# SAMV71_Xplained_Ultra_Ethernet.net
KiCad netlist of a schematic drawn in Altium Designer
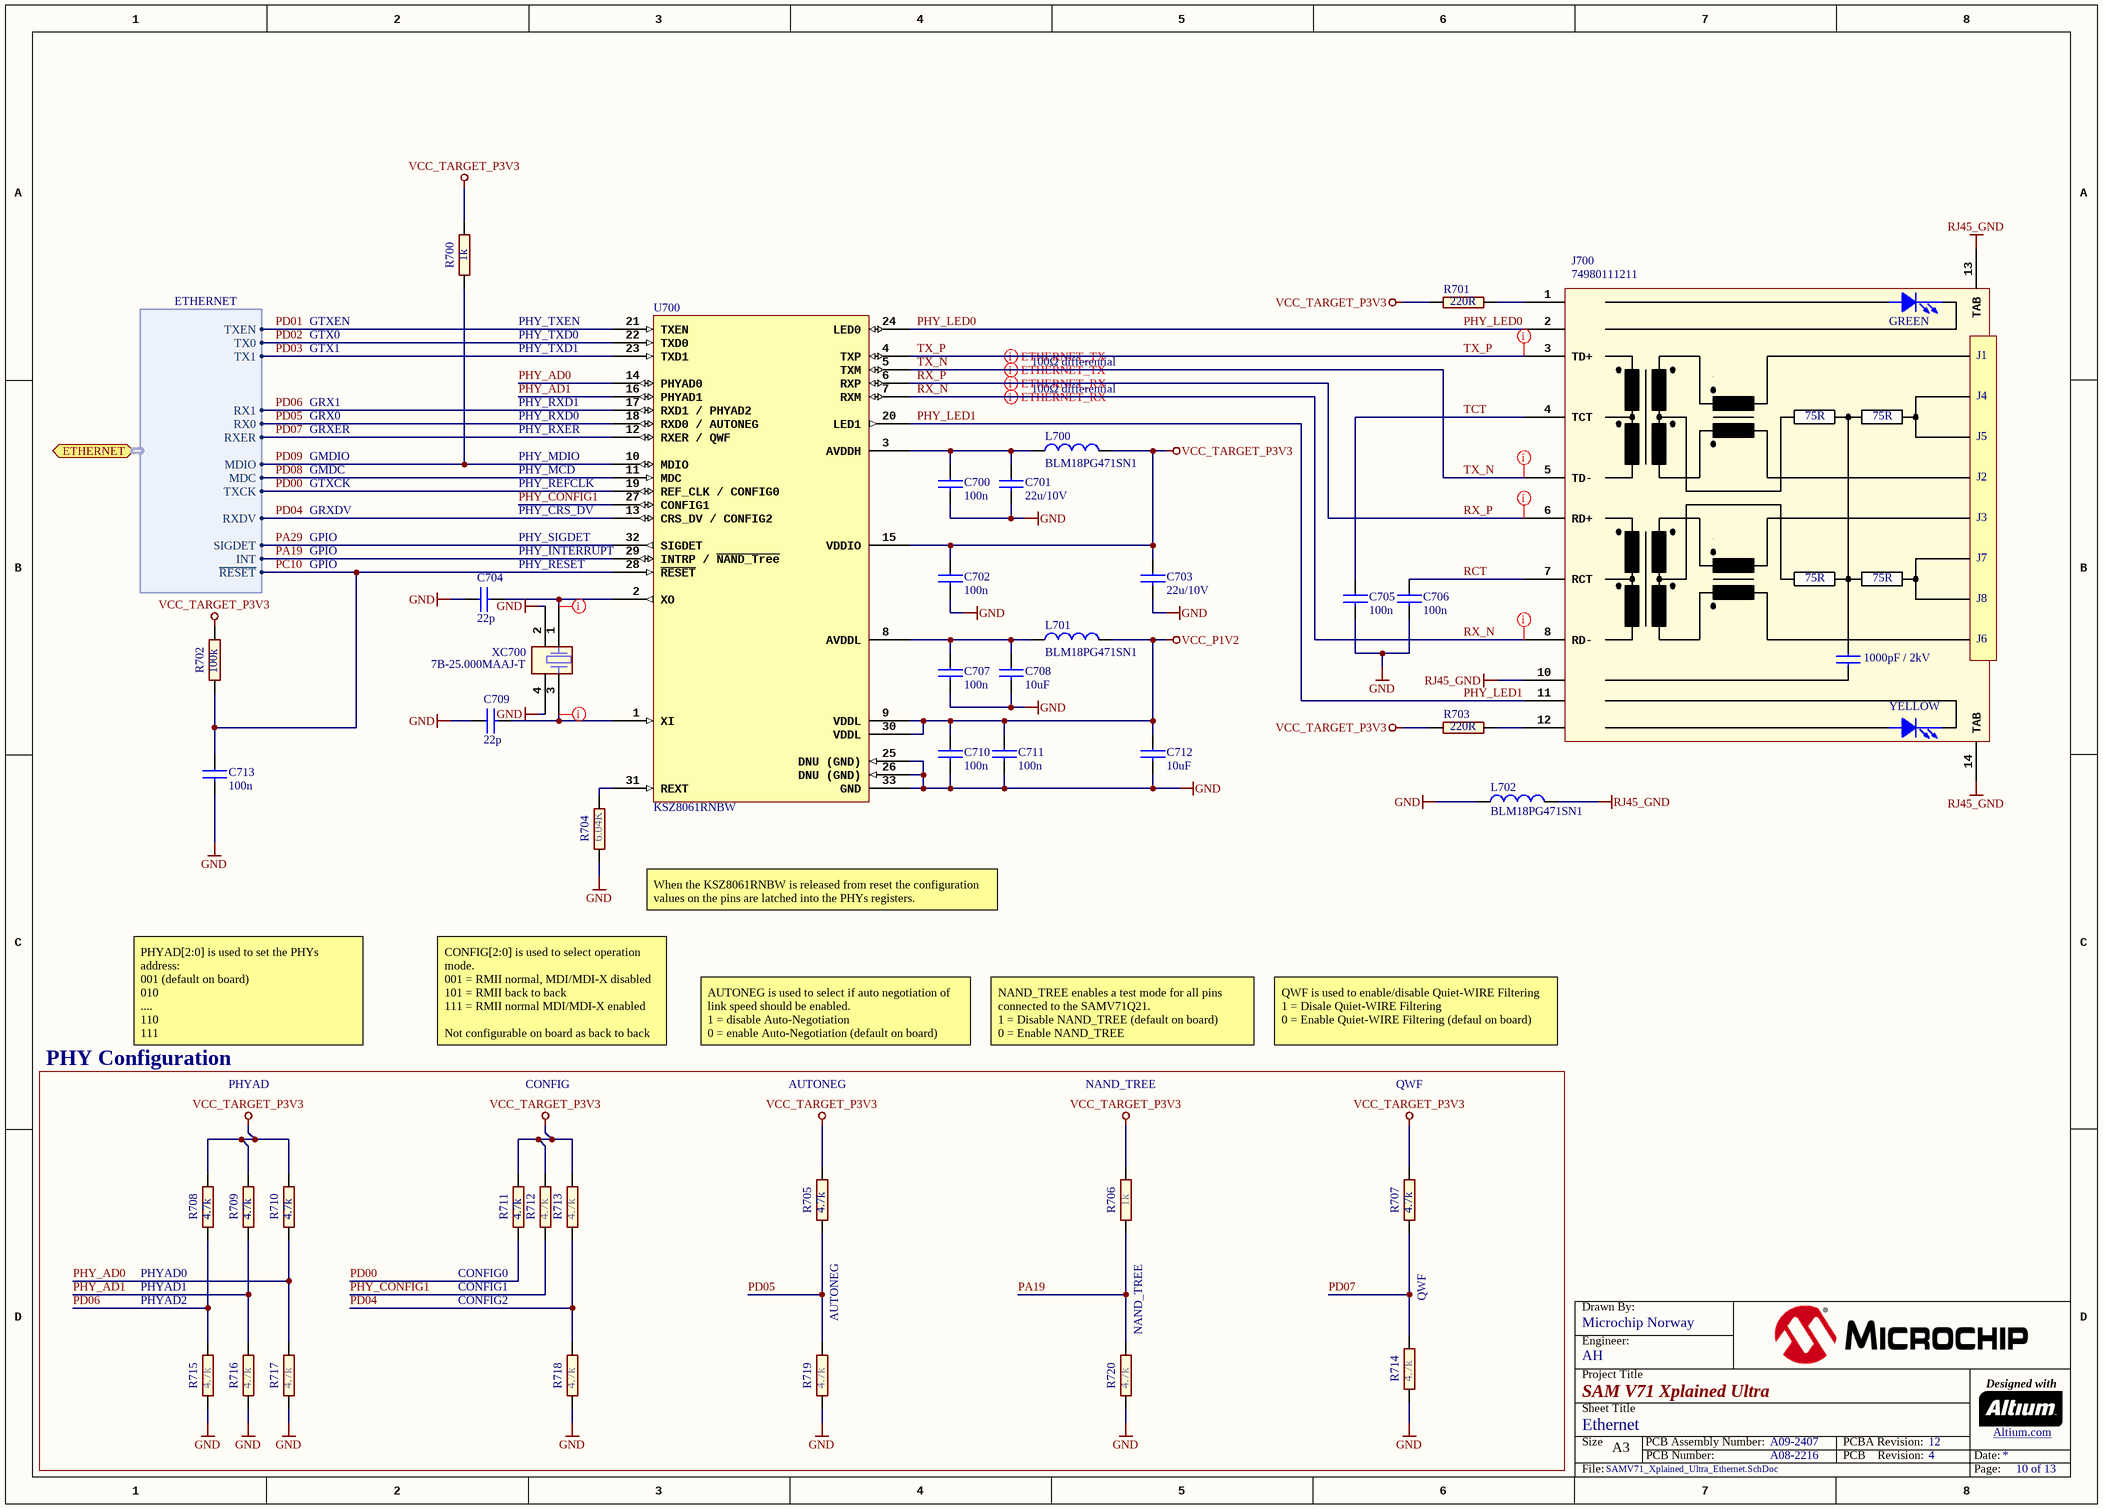
[diagram p0: SAMV71_Xplained_Ultra_Ethernet.SchDoc]

(export (version "E")
  (design (tool "Eeschema 10.0.6"))
  (components
    (comp (ref "C700")
      (value "100n")
      (footprint "AP1-00001")
      (description "Ceramic capacitor, SMD 0402, X7R, 16V, +/-10%")
      (fields (field (name "TOLERANCE") "16V, +/-10%") (field (name "MANUFACTURER") "Kemet"))
      (libsource (lib "AltiumDbLib") (part "CAP-NONPOL"))
    )
    (comp (ref "C701")
      (value "22u/10V")
      (footprint "AP1-00003")
      (description "Ceramic capacitor, SMD 0805, X5R, 10V, ±20%")
      (fields (field (name "MANUFACTURER") "tdk") (field (name "MPN") "C2012X5R1A226M/0.85"))
      (libsource (lib "AltiumDbLib") (part "CAP-NONPOL"))
    )
    (comp (ref "C702")
      (value "100n")
      (footprint "AP1-00001")
      (description "Ceramic capacitor, SMD 0402, X7R, 16V, +/-10%")
      (fields (field (name "TOLERANCE") "16V, +/-10%") (field (name "MANUFACTURER") "Kemet"))
      (libsource (lib "AltiumDbLib") (part "CAP-NONPOL"))
    )
    (comp (ref "C703")
      (value "22u/10V")
      (footprint "AP1-00003")
      (description "Ceramic capacitor, SMD 0805, X5R, 10V, ±20%")
      (fields (field (name "MANUFACTURER") "tdk") (field (name "MPN") "C2012X5R1A226M/0.85"))
      (libsource (lib "AltiumDbLib") (part "CAP-NONPOL"))
    )
    (comp (ref "C704")
      (value "22p")
      (footprint "AP1-00001")
      (description "Ceramic capacitor, SMD 0402, NP0, 50V, +/-5%")
      (fields (field (name "TOLERANCE") "50V, +/-5%") (field (name "MANUFACTURER") "YAGEO CORP"))
      (libsource (lib "AltiumDbLib") (part "CAP-NONPOL"))
    )
    (comp (ref "C705")
      (value "100n")
      (footprint "AP1-00001")
      (description "Ceramic capacitor, SMD 0402, X7R, 16V, +/-10%")
      (fields (field (name "TOLERANCE") "16V, +/-10%") (field (name "MANUFACTURER") "Kemet"))
      (libsource (lib "AltiumDbLib") (part "CAP-NONPOL"))
    )
    (comp (ref "C706")
      (value "100n")
      (footprint "AP1-00001")
      (description "Ceramic capacitor, SMD 0402, X7R, 16V, +/-10%")
      (fields (field (name "TOLERANCE") "16V, +/-10%") (field (name "MANUFACTURER") "Kemet"))
      (libsource (lib "AltiumDbLib") (part "CAP-NONPOL"))
    )
    (comp (ref "C707")
      (value "100n")
      (footprint "AP1-00001")
      (description "Ceramic capacitor, SMD 0402, X7R, 16V, +/-10%")
      (fields (field (name "TOLERANCE") "16V, +/-10%") (field (name "MANUFACTURER") "Kemet"))
      (libsource (lib "AltiumDbLib") (part "CAP-NONPOL"))
    )
    (comp (ref "C708")
      (value "10uF")
      (footprint "AP1-00041")
      (description "Ceramic capacitor, SMD 0805, X7R, 10V, 10 %, (de19441)")
      (fields (field (name "TOLERANCE") "10%") (field (name "MANUFACTURER") "Murata"))
      (libsource (lib "AltiumDbLib") (part "CAP-NONPOL"))
    )
    (comp (ref "C709")
      (value "22p")
      (footprint "AP1-00001")
      (description "Ceramic capacitor, SMD 0402, NP0, 50V, +/-5%")
      (fields (field (name "TOLERANCE") "50V, +/-5%") (field (name "MANUFACTURER") "YAGEO CORP"))
      (libsource (lib "AltiumDbLib") (part "CAP-NONPOL"))
    )
    (comp (ref "C710")
      (value "100n")
      (footprint "AP1-00001")
      (description "Ceramic capacitor, SMD 0402, X7R, 16V, +/-10%")
      (fields (field (name "TOLERANCE") "16V, +/-10%") (field (name "MANUFACTURER") "Kemet"))
      (libsource (lib "AltiumDbLib") (part "CAP-NONPOL"))
    )
    (comp (ref "C711")
      (value "100n")
      (footprint "AP1-00001")
      (description "Ceramic capacitor, SMD 0402, X7R, 16V, +/-10%")
      (fields (field (name "TOLERANCE") "16V, +/-10%") (field (name "MANUFACTURER") "Kemet"))
      (libsource (lib "AltiumDbLib") (part "CAP-NONPOL"))
    )
    (comp (ref "C712")
      (value "10uF")
      (footprint "AP1-00041")
      (description "Ceramic capacitor, SMD 0805, X7R, 10V, 10 %, (de19441)")
      (fields (field (name "TOLERANCE") "10%") (field (name "MANUFACTURER") "Murata"))
      (libsource (lib "AltiumDbLib") (part "CAP-NONPOL"))
    )
    (comp (ref "C713")
      (value "100n")
      (footprint "AP1-00001")
      (description "Ceramic capacitor, SMD 0402, X7R, 16V, +/-10%")
      (fields (field (name "TOLERANCE") "16V, +/-10%") (field (name "MANUFACTURER") "Kemet"))
      (libsource (lib "AltiumDbLib") (part "CAP-NONPOL"))
    )
    (comp (ref "J700")
      (value "74980111211")
      (footprint "AP8-00749")
      (description "10/100Base-TX, SMD, RJ45, green and yellow LEDs, integrated magnetics")
      (fields (field (name "MANUFACTURER") "Wurth Elektronik"))
      (libsource (lib "AltiumDbLib") (part "74980111211"))
    )
    (comp (ref "L700")
      (value "BLM18PG471SN1")
      (footprint "AP3-00005")
      (description "SMD RF inductor 0603. Z=470Ohm (@100MHz), Max R(dc)=0.65Ohm, Max current=1A")
      (fields (field (name "MANUFACTURER") "Murata"))
      (libsource (lib "AltiumDbLib") (part "INDUCTOR"))
    )
    (comp (ref "L701")
      (value "BLM18PG471SN1")
      (footprint "AP3-00005")
      (description "SMD RF inductor 0603. Z=470Ohm (@100MHz), Max R(dc)=0.65Ohm, Max current=1A")
      (fields (field (name "MANUFACTURER") "Murata"))
      (libsource (lib "AltiumDbLib") (part "INDUCTOR"))
    )
    (comp (ref "L702")
      (value "BLM18PG471SN1")
      (footprint "AP3-00005")
      (description "SMD RF inductor 0603. Z=470Ohm (@100MHz), Max R(dc)=0.65Ohm, Max current=1A")
      (fields (field (name "MANUFACTURER") "Murata"))
      (libsource (lib "") (part "INDUCTOR_1"))
    )
    (comp (ref "R700")
      (value "1k")
      (footprint "AP2-00000")
      (description "Thick film resistor, SMD 0402, 1/16W, 1%")
      (fields (field (name "TOLERANCE") "1 %") (field (name "MANUFACTURER") "ASJ"))
      (libsource (lib "AltiumDbLib") (part "R2"))
    )
    (comp (ref "R701")
      (value "220R")
      (footprint "AP2-00000")
      (description "Thick film resistor, SMD 0402, 1/16W, 1%")
      (fields (field (name "TOLERANCE") "1 %") (field (name "MANUFACTURER") "ASJ"))
      (libsource (lib "") (part "R2_3"))
    )
    (comp (ref "R702")
      (value "100k")
      (footprint "AP2-00000")
      (description "Thick film resistor, SMD 0402, 1/16W, 1%")
      (fields (field (name "TOLERANCE") "1 %") (field (name "MANUFACTURER") "ASJ"))
      (libsource (lib "AltiumDbLib") (part "R2"))
    )
    (comp (ref "R703")
      (value "220R")
      (footprint "AP2-00000")
      (description "Thick film resistor, SMD 0402, 1/16W, 1%")
      (fields (field (name "TOLERANCE") "1 %") (field (name "MANUFACTURER") "ASJ"))
      (libsource (lib "") (part "R2_2"))
    )
    (comp (ref "R704")
      (value "6.04K")
      (footprint "AP2-00000")
      (description "Thick film resistor, SMD 0402, 1/16W, 1%, E192")
      (fields (field (name "TOLERANCE") "1%"))
      (libsource (lib "AltiumDbLib") (part "R2"))
    )
    (comp (ref "R705")
      (value "4.7k")
      (footprint "AP2-00000")
      (description "Thick film resistor, SMD 0402, 1/16W, 1%")
      (fields (field (name "TOLERANCE") "1 %") (field (name "MANUFACTURER") "PHYCOMP"))
      (libsource (lib "AltiumDbLib") (part "R2"))
    )
    (comp (ref "R706")
      (value "1k")
      (footprint "AP2-00000")
      (description "Thick film resistor, SMD 0402, 1/16W, 1%")
      (fields (field (name "TOLERANCE") "1 %") (field (name "MANUFACTURER") "ASJ"))
      (libsource (lib "AltiumDbLib") (part "R2"))
    )
    (comp (ref "R707")
      (value "4.7k")
      (footprint "AP2-00000")
      (description "Thick film resistor, SMD 0402, 1/16W, 1%")
      (fields (field (name "TOLERANCE") "1 %") (field (name "MANUFACTURER") "PHYCOMP"))
      (libsource (lib "AltiumDbLib") (part "R2"))
    )
    (comp (ref "R708")
      (value "4.7k")
      (footprint "AP2-00000")
      (description "Thick film resistor, SMD 0402, 1/16W, 1%")
      (fields (field (name "TOLERANCE") "1 %") (field (name "MANUFACTURER") "PHYCOMP"))
      (libsource (lib "AltiumDbLib") (part "R2"))
    )
    (comp (ref "R709")
      (value "4.7k")
      (footprint "AP2-00000")
      (description "Thick film resistor, SMD 0402, 1/16W, 1%")
      (fields (field (name "TOLERANCE") "1 %") (field (name "MANUFACTURER") "PHYCOMP"))
      (libsource (lib "AltiumDbLib") (part "R2"))
    )
    (comp (ref "R710")
      (value "4.7k")
      (footprint "AP2-00000")
      (description "Thick film resistor, SMD 0402, 1/16W, 1%")
      (fields (field (name "TOLERANCE") "1 %") (field (name "MANUFACTURER") "PHYCOMP"))
      (libsource (lib "AltiumDbLib") (part "R2"))
    )
    (comp (ref "R711")
      (value "4.7k")
      (footprint "AP2-00000")
      (description "Thick film resistor, SMD 0402, 1/16W, 1%")
      (fields (field (name "TOLERANCE") "1 %") (field (name "MANUFACTURER") "PHYCOMP"))
      (libsource (lib "AltiumDbLib") (part "R2"))
    )
    (comp (ref "R712")
      (value "4.7k")
      (footprint "AP2-00000")
      (description "Thick film resistor, SMD 0402, 1/16W, 1%")
      (fields (field (name "TOLERANCE") "1 %") (field (name "MANUFACTURER") "PHYCOMP"))
      (libsource (lib "AltiumDbLib") (part "R2"))
    )
    (comp (ref "R713")
      (value "4.7k")
      (footprint "AP2-00000")
      (description "Thick film resistor, SMD 0402, 1/16W, 1%")
      (fields (field (name "TOLERANCE") "1 %") (field (name "MANUFACTURER") "PHYCOMP"))
      (libsource (lib "AltiumDbLib") (part "R2"))
    )
    (comp (ref "R714")
      (value "4.7k")
      (footprint "AP2-00000")
      (description "Thick film resistor, SMD 0402, 1/16W, 1%")
      (fields (field (name "TOLERANCE") "1 %") (field (name "MANUFACTURER") "PHYCOMP"))
      (libsource (lib "") (part "R2_1"))
    )
    (comp (ref "R715")
      (value "4.7k")
      (footprint "AP2-00000")
      (description "Thick film resistor, SMD 0402, 1/16W, 1%")
      (fields (field (name "TOLERANCE") "1 %") (field (name "MANUFACTURER") "PHYCOMP"))
      (libsource (lib "") (part "R2_1"))
    )
    (comp (ref "R716")
      (value "4.7k")
      (footprint "AP2-00000")
      (description "Thick film resistor, SMD 0402, 1/16W, 1%")
      (fields (field (name "TOLERANCE") "1 %") (field (name "MANUFACTURER") "PHYCOMP"))
      (libsource (lib "") (part "R2_1"))
    )
    (comp (ref "R717")
      (value "4.7k")
      (footprint "AP2-00000")
      (description "Thick film resistor, SMD 0402, 1/16W, 1%")
      (fields (field (name "TOLERANCE") "1 %") (field (name "MANUFACTURER") "PHYCOMP"))
      (libsource (lib "") (part "R2_1"))
    )
    (comp (ref "R718")
      (value "4.7k")
      (footprint "AP2-00000")
      (description "Thick film resistor, SMD 0402, 1/16W, 1%")
      (fields (field (name "TOLERANCE") "1 %") (field (name "MANUFACTURER") "PHYCOMP"))
      (libsource (lib "AltiumDbLib") (part "R2"))
    )
    (comp (ref "R719")
      (value "4.7k")
      (footprint "AP2-00000")
      (description "Thick film resistor, SMD 0402, 1/16W, 1%")
      (fields (field (name "TOLERANCE") "1 %") (field (name "MANUFACTURER") "PHYCOMP"))
      (libsource (lib "") (part "R2_1"))
    )
    (comp (ref "R720")
      (value "4.7k")
      (footprint "AP2-00000")
      (description "Thick film resistor, SMD 0402, 1/16W, 1%")
      (fields (field (name "TOLERANCE") "1 %") (field (name "MANUFACTURER") "PHYCOMP"))
      (libsource (lib "") (part "R2_1"))
    )
    (comp (ref "U700")
      (value "KSZ8061RNBW")
      (footprint "AP6-00349")
      (description "10Base-T/100Base-TX PHY, RMII, EEE, 50MHz clock output")
      (fields
        (field (name "MANUFACTURER") "Microchip")
        (field (name "Comment") "Industrial Extended Temperature")
      )
      (libsource (lib "AltiumDbLib") (part "KSZ8061RNB"))
    )
    (comp (ref "XC700")
      (value "7B-25.000MAAJ-T")
      (footprint "AP7-00067")
      (description "25.000 MHz crystal, 18pF, ±30ppm, 5.0 x 3.2 mm")
      (fields (field (name "TOLERANCE") "Â±30ppm") (field (name "MANUFACTURER") "TXC Corporation"))
      (libsource (lib "AltiumDbLib") (part "CRYSTAL1324"))
    )
  )
  (nets
    (net (code "2") (name "/PA19") (class "Default")
      (node (ref "R706") (pin "1") (pinfunction "1_1") (pintype "passive"))
      (node (ref "R720") (pin "1") (pinfunction "1_1") (pintype "passive"))
      (node (ref "U700") (pin "29") (pinfunction "INTRP_/_~{NAND_Tree}_29") (pintype "bidirectional"))
    )
    (net (code "3") (name "/PA29") (class "Default")
      (node (ref "U700") (pin "32") (pinfunction "SIGDET_32") (pintype "output"))
    )
    (net (code "4") (name "/PC10") (class "Default")
      (node (ref "C713") (pin "1") (pinfunction "1_1") (pintype "passive"))
      (node (ref "R702") (pin "1") (pinfunction "1_1") (pintype "passive"))
      (node (ref "U700") (pin "28") (pinfunction "~{RESET}_28") (pintype "input"))
    )
    (net (code "5") (name "/PD00") (class "Default")
      (node (ref "R711") (pin "1") (pinfunction "1_1") (pintype "passive"))
      (node (ref "U700") (pin "19") (pinfunction "REF_CLK_/_CONFIG0_19") (pintype "bidirectional"))
    )
    (net (code "6") (name "/PD01") (class "Default")
      (node (ref "U700") (pin "21") (pinfunction "TXEN_21") (pintype "input"))
    )
    (net (code "7") (name "/PD02") (class "Default")
      (node (ref "U700") (pin "22") (pinfunction "TXD0_22") (pintype "input"))
    )
    (net (code "8") (name "/PD03") (class "Default")
      (node (ref "U700") (pin "23") (pinfunction "TXD1_23") (pintype "input"))
    )
    (net (code "9") (name "/PD04") (class "Default")
      (node (ref "R713") (pin "1") (pinfunction "1_1") (pintype "passive"))
      (node (ref "R718") (pin "2") (pinfunction "2_2") (pintype "passive"))
      (node (ref "U700") (pin "13") (pinfunction "CRS_DV_/_CONFIG2_13") (pintype "bidirectional"))
    )
    (net (code "10") (name "/PD05") (class "Default")
      (node (ref "R705") (pin "1") (pinfunction "1_1") (pintype "passive"))
      (node (ref "R719") (pin "1") (pinfunction "1_1") (pintype "passive"))
      (node (ref "U700") (pin "18") (pinfunction "RXD0_/_AUTONEG_18") (pintype "bidirectional"))
    )
    (net (code "11") (name "/PD06") (class "Default")
      (node (ref "R708") (pin "1") (pinfunction "1_1") (pintype "passive"))
      (node (ref "R715") (pin "1") (pinfunction "1_1") (pintype "passive"))
      (node (ref "U700") (pin "17") (pinfunction "RXD1_/_PHYAD2_17") (pintype "bidirectional"))
    )
    (net (code "12") (name "/PD07") (class "Default")
      (node (ref "R707") (pin "1") (pinfunction "1_1") (pintype "passive"))
      (node (ref "R714") (pin "1") (pinfunction "1_1") (pintype "passive"))
      (node (ref "U700") (pin "12") (pinfunction "RXER_/_QWF_12") (pintype "bidirectional"))
    )
    (net (code "13") (name "/PD08") (class "Default")
      (node (ref "U700") (pin "11") (pinfunction "MDC_11") (pintype "input"))
    )
    (net (code "14") (name "/PD09") (class "Default")
      (node (ref "R700") (pin "1") (pinfunction "1_1") (pintype "passive"))
      (node (ref "U700") (pin "10") (pinfunction "MDIO_10") (pintype "bidirectional"))
    )
    (net (code "15") (name "/PHY_AD0") (class "Default")
      (node (ref "R710") (pin "1") (pinfunction "1_1") (pintype "passive"))
      (node (ref "R717") (pin "1") (pinfunction "1_1") (pintype "passive"))
      (node (ref "U700") (pin "14") (pinfunction "PHYAD0_14") (pintype "bidirectional"))
    )
    (net (code "16") (name "/PHY_AD1") (class "Default")
      (node (ref "R709") (pin "1") (pinfunction "1_1") (pintype "passive"))
      (node (ref "R716") (pin "1") (pinfunction "1_1") (pintype "passive"))
      (node (ref "U700") (pin "16") (pinfunction "PHYAD1_16") (pintype "bidirectional"))
    )
    (net (code "17") (name "/PHY_CONFIG1") (class "Default")
      (node (ref "R712") (pin "1") (pinfunction "1_1") (pintype "passive"))
      (node (ref "U700") (pin "27") (pinfunction "CONFIG1_27") (pintype "bidirectional"))
    )
    (net (code "18") (name "/PHY_LED0") (class "Default")
      (node (ref "J700") (pin "2") (pintype "passive"))
      (node (ref "U700") (pin "24") (pinfunction "LED0_24") (pintype "bidirectional"))
    )
    (net (code "19") (name "/PHY_LED1") (class "Default")
      (node (ref "J700") (pin "11") (pintype "passive"))
      (node (ref "U700") (pin "20") (pinfunction "LED1_20") (pintype "output"))
    )
    (net (code "20") (name "/RCT") (class "Default")
      (node (ref "C706") (pin "1") (pinfunction "1_1") (pintype "passive"))
      (node (ref "J700") (pin "7") (pinfunction "RCT_7") (pintype "passive"))
    )
    (net (code "21") (name "/RX_N") (class "Default")
      (node (ref "J700") (pin "8") (pinfunction "RD-_8") (pintype "passive"))
      (node (ref "U700") (pin "7") (pinfunction "RXM_7") (pintype "bidirectional"))
    )
    (net (code "22") (name "/RX_P") (class "Default")
      (node (ref "J700") (pin "6") (pinfunction "RD+_6") (pintype "passive"))
      (node (ref "U700") (pin "6") (pinfunction "RXP_6") (pintype "bidirectional"))
    )
    (net (code "23") (name "/TCT") (class "Default")
      (node (ref "C705") (pin "1") (pinfunction "1_1") (pintype "passive"))
      (node (ref "J700") (pin "4") (pinfunction "TCT_4") (pintype "passive"))
    )
    (net (code "24") (name "/TX_N") (class "Default")
      (node (ref "J700") (pin "5") (pinfunction "TD-_5") (pintype "passive"))
      (node (ref "U700") (pin "5") (pinfunction "TXM_5") (pintype "bidirectional"))
    )
    (net (code "25") (name "/TX_P") (class "Default")
      (node (ref "J700") (pin "3") (pinfunction "TD+_3") (pintype "passive"))
      (node (ref "U700") (pin "4") (pinfunction "TXP_4") (pintype "bidirectional"))
    )
    (net (code "27") (name "GND") (class "Default")
      (node (ref "C700") (pin "2") (pinfunction "2_2") (pintype "passive"))
      (node (ref "C701") (pin "2") (pinfunction "2_2") (pintype "passive"))
      (node (ref "C702") (pin "2") (pinfunction "2_2") (pintype "passive"))
      (node (ref "C703") (pin "2") (pinfunction "2_2") (pintype "passive"))
      (node (ref "C704") (pin "1") (pinfunction "1_1") (pintype "passive"))
      (node (ref "C705") (pin "2") (pinfunction "2_2") (pintype "passive"))
      (node (ref "C706") (pin "2") (pinfunction "2_2") (pintype "passive"))
      (node (ref "C707") (pin "2") (pinfunction "2_2") (pintype "passive"))
      (node (ref "C708") (pin "2") (pinfunction "2_2") (pintype "passive"))
      (node (ref "C709") (pin "1") (pinfunction "1_1") (pintype "passive"))
      (node (ref "C710") (pin "2") (pinfunction "2_2") (pintype "passive"))
      (node (ref "C711") (pin "2") (pinfunction "2_2") (pintype "passive"))
      (node (ref "C712") (pin "2") (pinfunction "2_2") (pintype "passive"))
      (node (ref "C713") (pin "2") (pinfunction "2_2") (pintype "passive"))
      (node (ref "L702") (pin "1") (pinfunction "1_1") (pintype "passive"))
      (node (ref "R704") (pin "1") (pinfunction "1_1") (pintype "passive"))
      (node (ref "R714") (pin "2") (pinfunction "2_2") (pintype "passive"))
      (node (ref "R715") (pin "2") (pinfunction "2_2") (pintype "passive"))
      (node (ref "R716") (pin "2") (pinfunction "2_2") (pintype "passive"))
      (node (ref "R717") (pin "2") (pinfunction "2_2") (pintype "passive"))
      (node (ref "R718") (pin "1") (pinfunction "1_1") (pintype "passive"))
      (node (ref "R719") (pin "2") (pinfunction "2_2") (pintype "passive"))
      (node (ref "R720") (pin "2") (pinfunction "2_2") (pintype "passive"))
      (node (ref "U700") (pin "25") (pinfunction "DNU_(GND)_25") (pintype "input"))
      (node (ref "U700") (pin "26") (pinfunction "DNU_(GND)_26") (pintype "input"))
      (node (ref "U700") (pin "33") (pinfunction "GND_33") (pintype "power_in"))
      (node (ref "XC700") (pin "2") (pinfunction "2_2") (pintype "passive"))
      (node (ref "XC700") (pin "4") (pinfunction "4_4") (pintype "passive"))
    )
    (net (code "28") (name "Net-(J700-Pad1)") (class "Default")
      (node (ref "J700") (pin "1") (pintype "passive"))
      (node (ref "R701") (pin "1") (pinfunction "1_1") (pintype "passive"))
    )
    (net (code "29") (name "Net-(J700-Pad12)") (class "Default")
      (node (ref "J700") (pin "12") (pintype "passive"))
      (node (ref "R703") (pin "2") (pinfunction "2_2") (pintype "passive"))
    )
    (net (code "30") (name "Net-(U700-AVDDH)") (class "Default")
      (node (ref "C700") (pin "1") (pinfunction "1_1") (pintype "passive"))
      (node (ref "C701") (pin "1") (pinfunction "1_1") (pintype "passive"))
      (node (ref "L700") (pin "2") (pinfunction "2_2") (pintype "passive"))
      (node (ref "U700") (pin "3") (pinfunction "AVDDH_3") (pintype "power_in"))
    )
    (net (code "31") (name "Net-(U700-AVDDL)") (class "Default")
      (node (ref "C707") (pin "1") (pinfunction "1_1") (pintype "passive"))
      (node (ref "C708") (pin "1") (pinfunction "1_1") (pintype "passive"))
      (node (ref "L701") (pin "2") (pinfunction "2_2") (pintype "passive"))
      (node (ref "U700") (pin "8") (pinfunction "AVDDL_8") (pintype "power_in"))
    )
    (net (code "32") (name "Net-(U700-REXT)") (class "Default")
      (node (ref "R704") (pin "2") (pinfunction "2_2") (pintype "passive"))
      (node (ref "U700") (pin "31") (pinfunction "REXT_31") (pintype "input"))
    )
    (net (code "33") (name "Net-(U700-XI)") (class "Default")
      (node (ref "C709") (pin "2") (pinfunction "2_2") (pintype "passive"))
      (node (ref "U700") (pin "1") (pinfunction "XI_1") (pintype "input"))
      (node (ref "XC700") (pin "3") (pinfunction "3_3") (pintype "passive"))
    )
    (net (code "34") (name "Net-(U700-XO)") (class "Default")
      (node (ref "C704") (pin "2") (pinfunction "2_2") (pintype "passive"))
      (node (ref "U700") (pin "2") (pinfunction "XO_2") (pintype "output"))
      (node (ref "XC700") (pin "1") (pinfunction "1_1") (pintype "passive"))
    )
    (net (code "35") (name "RJ45_GND") (class "Default")
      (node (ref "J700") (pin "10") (pintype "passive"))
      (node (ref "J700") (pin "13") (pinfunction "TAB_13") (pintype "power_in"))
      (node (ref "J700") (pin "14") (pinfunction "TAB_14") (pintype "power_in"))
      (node (ref "L702") (pin "2") (pinfunction "2_2") (pintype "passive"))
    )
    (net (code "36") (name "VCC_P1V2") (class "Default")
      (node (ref "C710") (pin "1") (pinfunction "1_1") (pintype "passive"))
      (node (ref "C711") (pin "1") (pinfunction "1_1") (pintype "passive"))
      (node (ref "C712") (pin "1") (pinfunction "1_1") (pintype "passive"))
      (node (ref "L701") (pin "1") (pinfunction "1_1") (pintype "passive"))
      (node (ref "U700") (pin "30") (pinfunction "VDDL_30") (pintype "power_in"))
      (node (ref "U700") (pin "9") (pinfunction "VDDL_9") (pintype "power_in"))
    )
    (net (code "37") (name "VCC_TARGET_P3V3") (class "Default")
      (node (ref "C702") (pin "1") (pinfunction "1_1") (pintype "passive"))
      (node (ref "C703") (pin "1") (pinfunction "1_1") (pintype "passive"))
      (node (ref "L700") (pin "1") (pinfunction "1_1") (pintype "passive"))
      (node (ref "R700") (pin "2") (pinfunction "2_2") (pintype "passive"))
      (node (ref "R701") (pin "2") (pinfunction "2_2") (pintype "passive"))
      (node (ref "R702") (pin "2") (pinfunction "2_2") (pintype "passive"))
      (node (ref "R703") (pin "1") (pinfunction "1_1") (pintype "passive"))
      (node (ref "R705") (pin "2") (pinfunction "2_2") (pintype "passive"))
      (node (ref "R706") (pin "2") (pinfunction "2_2") (pintype "passive"))
      (node (ref "R707") (pin "2") (pinfunction "2_2") (pintype "passive"))
      (node (ref "R708") (pin "2") (pinfunction "2_2") (pintype "passive"))
      (node (ref "R709") (pin "2") (pinfunction "2_2") (pintype "passive"))
      (node (ref "R710") (pin "2") (pinfunction "2_2") (pintype "passive"))
      (node (ref "R711") (pin "2") (pinfunction "2_2") (pintype "passive"))
      (node (ref "R712") (pin "2") (pinfunction "2_2") (pintype "passive"))
      (node (ref "R713") (pin "2") (pinfunction "2_2") (pintype "passive"))
      (node (ref "U700") (pin "15") (pinfunction "VDDIO_15") (pintype "power_in"))
    )
  )
)
